# relay-set-d-latch.net
KiCad netlist of a schematic drawn in EAGLE
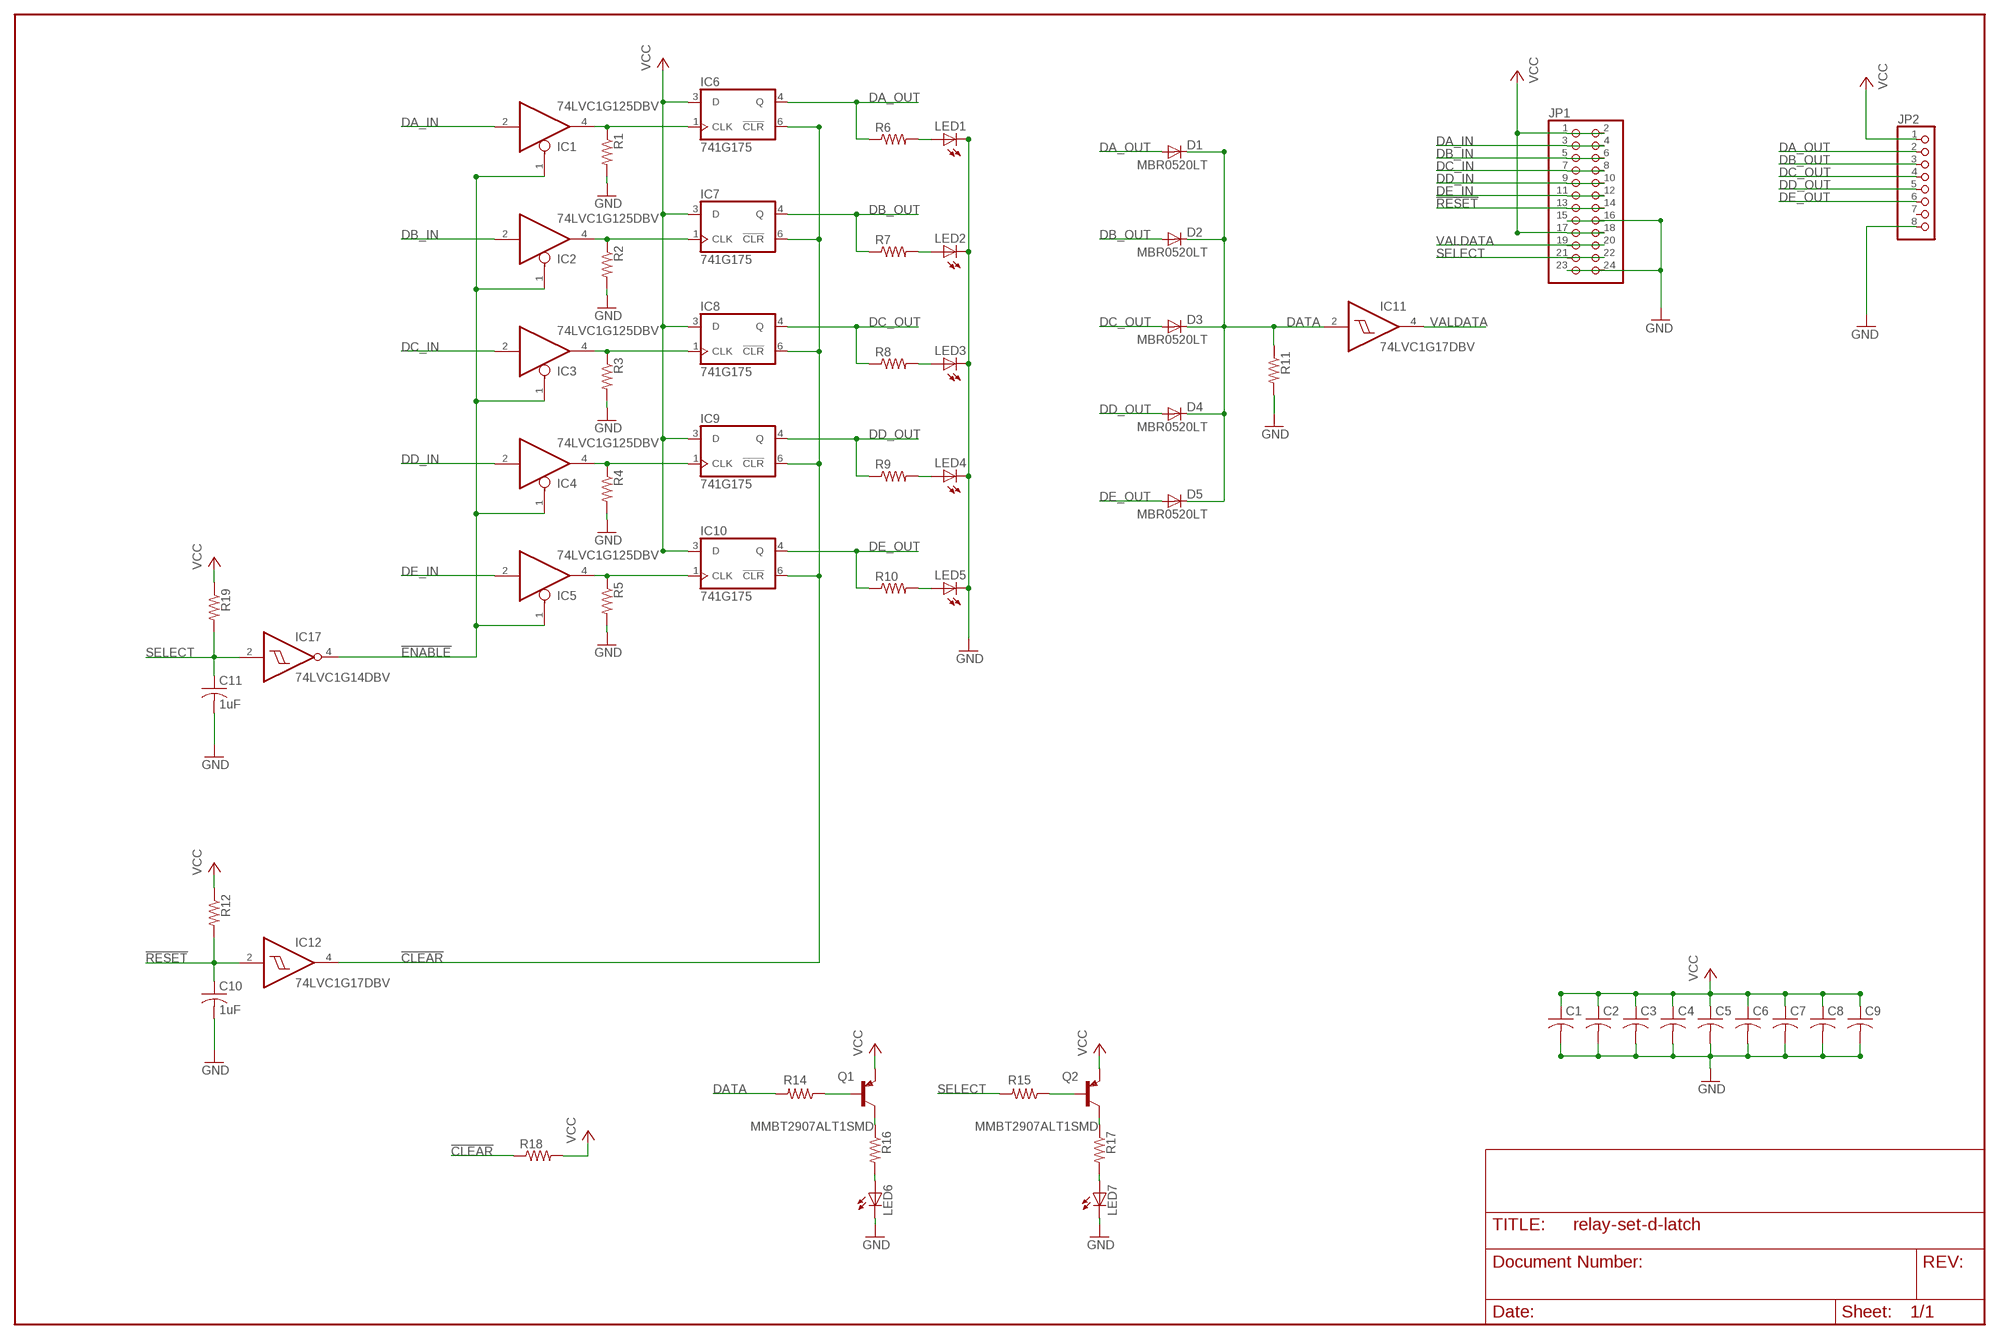
[diagram p0: schematic, sheet 1]

(export (version "E")
  (design (tool "Eeschema 10.0.6"))
  (components
    (comp (ref "C1")
      (value "C-USC0805")
      (footprint "eagle-import:C0805")
      (libsource (lib "eagle-import") (part "C-USC0805"))
    )
    (comp (ref "C2")
      (value "C-USC0805")
      (footprint "eagle-import:C0805")
      (libsource (lib "eagle-import") (part "C-USC0805"))
    )
    (comp (ref "C3")
      (value "C-USC0805")
      (footprint "eagle-import:C0805")
      (libsource (lib "eagle-import") (part "C-USC0805"))
    )
    (comp (ref "C4")
      (value "C-USC0805")
      (footprint "eagle-import:C0805")
      (libsource (lib "eagle-import") (part "C-USC0805"))
    )
    (comp (ref "C5")
      (value "C-USC0603K")
      (footprint "eagle-import:C0603K")
      (libsource (lib "eagle-import") (part "C-USC0603K"))
    )
    (comp (ref "C6")
      (value "C-USC0603K")
      (footprint "eagle-import:C0603K")
      (libsource (lib "eagle-import") (part "C-USC0603K"))
    )
    (comp (ref "C7")
      (value "C-USC0603K")
      (footprint "eagle-import:C0603K")
      (libsource (lib "eagle-import") (part "C-USC0603K"))
    )
    (comp (ref "C8")
      (value "C-USC0603K")
      (footprint "eagle-import:C0603K")
      (libsource (lib "eagle-import") (part "C-USC0603K"))
    )
    (comp (ref "C9")
      (value "C-USC0603K")
      (footprint "eagle-import:C0603K")
      (libsource (lib "eagle-import") (part "C-USC0603K"))
    )
    (comp (ref "C10")
      (value "1uF")
      (footprint "eagle-import:C0603K")
      (libsource (lib "eagle-import") (part "C-USC0603K"))
    )
    (comp (ref "C11")
      (value "1uF")
      (footprint "eagle-import:C0603K")
      (libsource (lib "eagle-import") (part "C-USC0603K"))
    )
    (comp (ref "D1")
      (value "MBR0520LT")
      (footprint "eagle-import:SOD123")
      (libsource (lib "eagle-import") (part "MBR0520LT"))
    )
    (comp (ref "D2")
      (value "MBR0520LT")
      (footprint "eagle-import:SOD123")
      (libsource (lib "eagle-import") (part "MBR0520LT"))
    )
    (comp (ref "D3")
      (value "MBR0520LT")
      (footprint "eagle-import:SOD123")
      (libsource (lib "eagle-import") (part "MBR0520LT"))
    )
    (comp (ref "D4")
      (value "MBR0520LT")
      (footprint "eagle-import:SOD123")
      (libsource (lib "eagle-import") (part "MBR0520LT"))
    )
    (comp (ref "D5")
      (value "MBR0520LT")
      (footprint "eagle-import:SOD123")
      (libsource (lib "eagle-import") (part "MBR0520LT"))
    )
    (comp (ref "IC1")
      (value "74LVC1G125DBV")
      (footprint "eagle-import:SOT23-5")
      (libsource (lib "eagle-import") (part "741G125DBVLVC"))
    )
    (comp (ref "IC2")
      (value "74LVC1G125DBV")
      (footprint "eagle-import:SOT23-5")
      (libsource (lib "eagle-import") (part "741G125DBVLVC"))
    )
    (comp (ref "IC3")
      (value "74LVC1G125DBV")
      (footprint "eagle-import:SOT23-5")
      (libsource (lib "eagle-import") (part "741G125DBVLVC"))
    )
    (comp (ref "IC4")
      (value "74LVC1G125DBV")
      (footprint "eagle-import:SOT23-5")
      (libsource (lib "eagle-import") (part "741G125DBVLVC"))
    )
    (comp (ref "IC5")
      (value "74LVC1G125DBV")
      (footprint "eagle-import:SOT23-5")
      (libsource (lib "eagle-import") (part "741G125DBVLVC"))
    )
    (comp (ref "IC6")
      (value "741G175")
      (footprint "eagle-import:DBV_R-PDSO-G6")
      (libsource (lib "eagle-import") (part "741G175"))
    )
    (comp (ref "IC7")
      (value "741G175")
      (footprint "eagle-import:DBV_R-PDSO-G6")
      (libsource (lib "eagle-import") (part "741G175"))
    )
    (comp (ref "IC8")
      (value "741G175")
      (footprint "eagle-import:DBV_R-PDSO-G6")
      (libsource (lib "eagle-import") (part "741G175"))
    )
    (comp (ref "IC9")
      (value "741G175")
      (footprint "eagle-import:DBV_R-PDSO-G6")
      (libsource (lib "eagle-import") (part "741G175"))
    )
    (comp (ref "IC10")
      (value "741G175")
      (footprint "eagle-import:DBV_R-PDSO-G6")
      (libsource (lib "eagle-import") (part "741G175"))
    )
    (comp (ref "IC11")
      (value "74LVC1G17DBV")
      (footprint "eagle-import:SOT23-5")
      (libsource (lib "eagle-import") (part "741G17DBVLVC"))
    )
    (comp (ref "IC12")
      (value "74LVC1G17DBV")
      (footprint "eagle-import:SOT23-5")
      (libsource (lib "eagle-import") (part "741G17DBVLVC"))
    )
    (comp (ref "IC17")
      (value "74LVC1G14DBV")
      (footprint "eagle-import:SOT23-5")
      (libsource (lib "eagle-import") (part "741G14DBVLVC"))
    )
    (comp (ref "JP1")
      (value "PINHD-2X12")
      (footprint "eagle-import:2X12")
      (libsource (lib "eagle-import") (part "PINHD-2X12"))
    )
    (comp (ref "JP2")
      (value "PINHD-1X8")
      (footprint "eagle-import:1X08")
      (libsource (lib "eagle-import") (part "PINHD-1X8"))
    )
    (comp (ref "LED1")
      (value "LEDCHIP-LED0805")
      (footprint "eagle-import:CHIP-LED0805")
      (libsource (lib "eagle-import") (part "LEDCHIP-LED0805"))
    )
    (comp (ref "LED2")
      (value "LEDCHIP-LED0805")
      (footprint "eagle-import:CHIP-LED0805")
      (libsource (lib "eagle-import") (part "LEDCHIP-LED0805"))
    )
    (comp (ref "LED3")
      (value "LEDCHIP-LED0805")
      (footprint "eagle-import:CHIP-LED0805")
      (libsource (lib "eagle-import") (part "LEDCHIP-LED0805"))
    )
    (comp (ref "LED4")
      (value "LEDCHIP-LED0805")
      (footprint "eagle-import:CHIP-LED0805")
      (libsource (lib "eagle-import") (part "LEDCHIP-LED0805"))
    )
    (comp (ref "LED5")
      (value "LEDCHIP-LED0805")
      (footprint "eagle-import:CHIP-LED0805")
      (libsource (lib "eagle-import") (part "LEDCHIP-LED0805"))
    )
    (comp (ref "LED6")
      (value "LEDCHIP-LED0805")
      (footprint "eagle-import:CHIP-LED0805")
      (libsource (lib "eagle-import") (part "LEDCHIP-LED0805"))
    )
    (comp (ref "LED7")
      (value "LEDCHIP-LED0805")
      (footprint "eagle-import:CHIP-LED0805")
      (libsource (lib "eagle-import") (part "LEDCHIP-LED0805"))
    )
    (comp (ref "Q1")
      (value "MMBT2907ALT1SMD")
      (footprint "eagle-import:SOT23-BEC")
      (libsource (lib "eagle-import") (part "MMBT2907SMDALT1"))
    )
    (comp (ref "Q2")
      (value "MMBT2907ALT1SMD")
      (footprint "eagle-import:SOT23-BEC")
      (libsource (lib "eagle-import") (part "MMBT2907SMDALT1"))
    )
    (comp (ref "R1")
      (value "R-US_R0805")
      (footprint "eagle-import:R0805")
      (libsource (lib "eagle-import") (part "R-US_R0805"))
    )
    (comp (ref "R2")
      (value "R-US_R0805")
      (footprint "eagle-import:R0805")
      (libsource (lib "eagle-import") (part "R-US_R0805"))
    )
    (comp (ref "R3")
      (value "R-US_R0805")
      (footprint "eagle-import:R0805")
      (libsource (lib "eagle-import") (part "R-US_R0805"))
    )
    (comp (ref "R4")
      (value "R-US_R0805")
      (footprint "eagle-import:R0805")
      (libsource (lib "eagle-import") (part "R-US_R0805"))
    )
    (comp (ref "R5")
      (value "R-US_R0805")
      (footprint "eagle-import:R0805")
      (libsource (lib "eagle-import") (part "R-US_R0805"))
    )
    (comp (ref "R6")
      (value "R-US_R0805")
      (footprint "eagle-import:R0805")
      (libsource (lib "eagle-import") (part "R-US_R0805"))
    )
    (comp (ref "R7")
      (value "R-US_R0805")
      (footprint "eagle-import:R0805")
      (libsource (lib "eagle-import") (part "R-US_R0805"))
    )
    (comp (ref "R8")
      (value "R-US_R0805")
      (footprint "eagle-import:R0805")
      (libsource (lib "eagle-import") (part "R-US_R0805"))
    )
    (comp (ref "R9")
      (value "R-US_R0805")
      (footprint "eagle-import:R0805")
      (libsource (lib "eagle-import") (part "R-US_R0805"))
    )
    (comp (ref "R10")
      (value "R-US_R0805")
      (footprint "eagle-import:R0805")
      (libsource (lib "eagle-import") (part "R-US_R0805"))
    )
    (comp (ref "R11")
      (value "R-US_R0805")
      (footprint "eagle-import:R0805")
      (libsource (lib "eagle-import") (part "R-US_R0805"))
    )
    (comp (ref "R12")
      (value "R-US_R0805")
      (footprint "eagle-import:R0805")
      (libsource (lib "eagle-import") (part "R-US_R0805"))
    )
    (comp (ref "R14")
      (value "R-US_R0805")
      (footprint "eagle-import:R0805")
      (libsource (lib "eagle-import") (part "R-US_R0805"))
    )
    (comp (ref "R15")
      (value "R-US_R0805")
      (footprint "eagle-import:R0805")
      (libsource (lib "eagle-import") (part "R-US_R0805"))
    )
    (comp (ref "R16")
      (value "R-US_R0805")
      (footprint "eagle-import:R0805")
      (libsource (lib "eagle-import") (part "R-US_R0805"))
    )
    (comp (ref "R17")
      (value "R-US_R0805")
      (footprint "eagle-import:R0805")
      (libsource (lib "eagle-import") (part "R-US_R0805"))
    )
    (comp (ref "R18")
      (value "R-US_R0805")
      (footprint "eagle-import:R0805")
      (libsource (lib "eagle-import") (part "R-US_R0805"))
    )
    (comp (ref "R19")
      (value "R-US_R0805")
      (footprint "eagle-import:R0805")
      (libsource (lib "eagle-import") (part "R-US_R0805"))
    )
  )
  (nets
    (net (code "1") (name "/DATA") (class "Default")
      (node (ref "D1") (pin "C") (pinfunction "C_C") (pintype "passive"))
      (node (ref "D2") (pin "C") (pinfunction "C_C") (pintype "passive"))
      (node (ref "D3") (pin "C") (pinfunction "C_C") (pintype "passive"))
      (node (ref "D4") (pin "C") (pinfunction "C_C") (pintype "passive"))
      (node (ref "D5") (pin "C") (pinfunction "C_C") (pintype "passive"))
      (node (ref "IC11") (pin "2") (pinfunction "I_2") (pintype "input"))
      (node (ref "R11") (pin "1") (pinfunction "1_1") (pintype "passive"))
      (node (ref "R14") (pin "2") (pinfunction "2_2") (pintype "passive"))
    )
    (net (code "2") (name "/DA_IN") (class "Default")
      (node (ref "IC1") (pin "2") (pinfunction "I_2") (pintype "input"))
      (node (ref "JP1") (pin "3") (pinfunction "3_3") (pintype "passive"))
      (node (ref "JP1") (pin "4") (pinfunction "4_4") (pintype "passive"))
    )
    (net (code "3") (name "/DA_OUT") (class "Default")
      (node (ref "D1") (pin "A") (pinfunction "A_A") (pintype "passive"))
      (node (ref "IC6") (pin "4") (pinfunction "Q_4") (pintype "output"))
      (node (ref "JP2") (pin "2") (pinfunction "2_2") (pintype "passive"))
      (node (ref "R6") (pin "1") (pinfunction "1_1") (pintype "passive"))
    )
    (net (code "4") (name "/DB_IN") (class "Default")
      (node (ref "IC2") (pin "2") (pinfunction "I_2") (pintype "input"))
      (node (ref "JP1") (pin "5") (pinfunction "5_5") (pintype "passive"))
      (node (ref "JP1") (pin "6") (pinfunction "6_6") (pintype "passive"))
    )
    (net (code "5") (name "/DB_OUT") (class "Default")
      (node (ref "D2") (pin "A") (pinfunction "A_A") (pintype "passive"))
      (node (ref "IC7") (pin "4") (pinfunction "Q_4") (pintype "output"))
      (node (ref "JP2") (pin "3") (pinfunction "3_3") (pintype "passive"))
      (node (ref "R7") (pin "1") (pinfunction "1_1") (pintype "passive"))
    )
    (net (code "6") (name "/DC_IN") (class "Default")
      (node (ref "IC3") (pin "2") (pinfunction "I_2") (pintype "input"))
      (node (ref "JP1") (pin "7") (pinfunction "7_7") (pintype "passive"))
      (node (ref "JP1") (pin "8") (pinfunction "8_8") (pintype "passive"))
    )
    (net (code "7") (name "/DC_OUT") (class "Default")
      (node (ref "D3") (pin "A") (pinfunction "A_A") (pintype "passive"))
      (node (ref "IC8") (pin "4") (pinfunction "Q_4") (pintype "output"))
      (node (ref "JP2") (pin "4") (pinfunction "4_4") (pintype "passive"))
      (node (ref "R8") (pin "1") (pinfunction "1_1") (pintype "passive"))
    )
    (net (code "8") (name "/DD_IN") (class "Default")
      (node (ref "IC4") (pin "2") (pinfunction "I_2") (pintype "input"))
      (node (ref "JP1") (pin "10") (pinfunction "10_10") (pintype "passive"))
      (node (ref "JP1") (pin "9") (pinfunction "9_9") (pintype "passive"))
    )
    (net (code "9") (name "/DD_OUT") (class "Default")
      (node (ref "D4") (pin "A") (pinfunction "A_A") (pintype "passive"))
      (node (ref "IC9") (pin "4") (pinfunction "Q_4") (pintype "output"))
      (node (ref "JP2") (pin "5") (pinfunction "5_5") (pintype "passive"))
      (node (ref "R9") (pin "1") (pinfunction "1_1") (pintype "passive"))
    )
    (net (code "10") (name "/DE_IN") (class "Default")
      (node (ref "IC5") (pin "2") (pinfunction "I_2") (pintype "input"))
      (node (ref "JP1") (pin "11") (pinfunction "11_11") (pintype "passive"))
      (node (ref "JP1") (pin "12") (pinfunction "12_12") (pintype "passive"))
    )
    (net (code "11") (name "/DE_OUT") (class "Default")
      (node (ref "D5") (pin "A") (pinfunction "A_A") (pintype "passive"))
      (node (ref "IC10") (pin "4") (pinfunction "Q_4") (pintype "output"))
      (node (ref "JP2") (pin "6") (pinfunction "6_6") (pintype "passive"))
      (node (ref "R10") (pin "1") (pinfunction "1_1") (pintype "passive"))
    )
    (net (code "12") (name "/SELECT") (class "Default")
      (node (ref "C11") (pin "1") (pinfunction "1_1") (pintype "passive"))
      (node (ref "IC17") (pin "2") (pinfunction "I_2") (pintype "input"))
      (node (ref "JP1") (pin "21") (pinfunction "21_21") (pintype "passive"))
      (node (ref "JP1") (pin "22") (pinfunction "22_22") (pintype "passive"))
      (node (ref "R15") (pin "2") (pinfunction "2_2") (pintype "passive"))
      (node (ref "R19") (pin "2") (pinfunction "2_2") (pintype "passive"))
    )
    (net (code "13") (name "/VALDATA") (class "Default")
      (node (ref "IC11") (pin "4") (pinfunction "O_4") (pintype "output"))
      (node (ref "JP1") (pin "19") (pinfunction "19_19") (pintype "passive"))
      (node (ref "JP1") (pin "20") (pinfunction "20_20") (pintype "passive"))
    )
    (net (code "14") (name "/~{CLEAR}") (class "Default")
      (node (ref "IC10") (pin "6") (pinfunction "~{CLR}_6") (pintype "output"))
      (node (ref "IC12") (pin "4") (pinfunction "O_4") (pintype "output"))
      (node (ref "IC6") (pin "6") (pinfunction "~{CLR}_6") (pintype "output"))
      (node (ref "IC7") (pin "6") (pinfunction "~{CLR}_6") (pintype "output"))
      (node (ref "IC8") (pin "6") (pinfunction "~{CLR}_6") (pintype "output"))
      (node (ref "IC9") (pin "6") (pinfunction "~{CLR}_6") (pintype "output"))
      (node (ref "R18") (pin "1") (pinfunction "1_1") (pintype "passive"))
    )
    (net (code "15") (name "/~{ENABLE}") (class "Default")
      (node (ref "IC1") (pin "1") (pinfunction "OE_1") (pintype "input"))
      (node (ref "IC17") (pin "4") (pinfunction "O_4") (pintype "output"))
      (node (ref "IC2") (pin "1") (pinfunction "OE_1") (pintype "input"))
      (node (ref "IC3") (pin "1") (pinfunction "OE_1") (pintype "input"))
      (node (ref "IC4") (pin "1") (pinfunction "OE_1") (pintype "input"))
      (node (ref "IC5") (pin "1") (pinfunction "OE_1") (pintype "input"))
    )
    (net (code "16") (name "/~{RESET}") (class "Default")
      (node (ref "C10") (pin "1") (pinfunction "1_1") (pintype "passive"))
      (node (ref "IC12") (pin "2") (pinfunction "I_2") (pintype "input"))
      (node (ref "JP1") (pin "13") (pinfunction "13_13") (pintype "passive"))
      (node (ref "JP1") (pin "14") (pinfunction "14_14") (pintype "passive"))
      (node (ref "R12") (pin "2") (pinfunction "2_2") (pintype "passive"))
    )
    (net (code "17") (name "GND") (class "Default")
      (node (ref "C1") (pin "2") (pinfunction "2_2") (pintype "passive"))
      (node (ref "C10") (pin "2") (pinfunction "2_2") (pintype "passive"))
      (node (ref "C11") (pin "2") (pinfunction "2_2") (pintype "passive"))
      (node (ref "C2") (pin "2") (pinfunction "2_2") (pintype "passive"))
      (node (ref "C3") (pin "2") (pinfunction "2_2") (pintype "passive"))
      (node (ref "C4") (pin "2") (pinfunction "2_2") (pintype "passive"))
      (node (ref "C5") (pin "2") (pinfunction "2_2") (pintype "passive"))
      (node (ref "C6") (pin "2") (pinfunction "2_2") (pintype "passive"))
      (node (ref "C7") (pin "2") (pinfunction "2_2") (pintype "passive"))
      (node (ref "C8") (pin "2") (pinfunction "2_2") (pintype "passive"))
      (node (ref "C9") (pin "2") (pinfunction "2_2") (pintype "passive"))
      (node (ref "JP1") (pin "15") (pinfunction "15_15") (pintype "passive"))
      (node (ref "JP1") (pin "16") (pinfunction "16_16") (pintype "passive"))
      (node (ref "JP1") (pin "23") (pinfunction "23_23") (pintype "passive"))
      (node (ref "JP1") (pin "24") (pinfunction "24_24") (pintype "passive"))
      (node (ref "JP2") (pin "8") (pinfunction "8_8") (pintype "passive"))
      (node (ref "LED1") (pin "C") (pinfunction "C_C") (pintype "passive"))
      (node (ref "LED2") (pin "C") (pinfunction "C_C") (pintype "passive"))
      (node (ref "LED3") (pin "C") (pinfunction "C_C") (pintype "passive"))
      (node (ref "LED4") (pin "C") (pinfunction "C_C") (pintype "passive"))
      (node (ref "LED5") (pin "C") (pinfunction "C_C") (pintype "passive"))
      (node (ref "LED6") (pin "C") (pinfunction "C_C") (pintype "passive"))
      (node (ref "LED7") (pin "C") (pinfunction "C_C") (pintype "passive"))
      (node (ref "R1") (pin "2") (pinfunction "2_2") (pintype "passive"))
      (node (ref "R11") (pin "2") (pinfunction "2_2") (pintype "passive"))
      (node (ref "R2") (pin "2") (pinfunction "2_2") (pintype "passive"))
      (node (ref "R3") (pin "2") (pinfunction "2_2") (pintype "passive"))
      (node (ref "R4") (pin "2") (pinfunction "2_2") (pintype "passive"))
      (node (ref "R5") (pin "2") (pinfunction "2_2") (pintype "passive"))
    )
    (net (code "18") (name "Net-(IC1A-O)") (class "Default")
      (node (ref "IC1") (pin "4") (pinfunction "O_4") (pintype "tri_state"))
      (node (ref "IC6") (pin "1") (pinfunction "CLK_1") (pintype "input"))
      (node (ref "R1") (pin "1") (pinfunction "1_1") (pintype "passive"))
    )
    (net (code "19") (name "Net-(IC2A-O)") (class "Default")
      (node (ref "IC2") (pin "4") (pinfunction "O_4") (pintype "tri_state"))
      (node (ref "IC7") (pin "1") (pinfunction "CLK_1") (pintype "input"))
      (node (ref "R2") (pin "1") (pinfunction "1_1") (pintype "passive"))
    )
    (net (code "20") (name "Net-(IC3A-O)") (class "Default")
      (node (ref "IC3") (pin "4") (pinfunction "O_4") (pintype "tri_state"))
      (node (ref "IC8") (pin "1") (pinfunction "CLK_1") (pintype "input"))
      (node (ref "R3") (pin "1") (pinfunction "1_1") (pintype "passive"))
    )
    (net (code "21") (name "Net-(IC4A-O)") (class "Default")
      (node (ref "IC4") (pin "4") (pinfunction "O_4") (pintype "tri_state"))
      (node (ref "IC9") (pin "1") (pinfunction "CLK_1") (pintype "input"))
      (node (ref "R4") (pin "1") (pinfunction "1_1") (pintype "passive"))
    )
    (net (code "22") (name "Net-(IC10A-CLK)") (class "Default")
      (node (ref "IC10") (pin "1") (pinfunction "CLK_1") (pintype "input"))
      (node (ref "IC5") (pin "4") (pinfunction "O_4") (pintype "tri_state"))
      (node (ref "R5") (pin "1") (pinfunction "1_1") (pintype "passive"))
    )
    (net (code "23") (name "Net-(LED1-PadA)") (class "Default")
      (node (ref "LED1") (pin "A") (pinfunction "A_A") (pintype "passive"))
      (node (ref "R6") (pin "2") (pinfunction "2_2") (pintype "passive"))
    )
    (net (code "24") (name "Net-(LED2-PadA)") (class "Default")
      (node (ref "LED2") (pin "A") (pinfunction "A_A") (pintype "passive"))
      (node (ref "R7") (pin "2") (pinfunction "2_2") (pintype "passive"))
    )
    (net (code "25") (name "Net-(LED3-PadA)") (class "Default")
      (node (ref "LED3") (pin "A") (pinfunction "A_A") (pintype "passive"))
      (node (ref "R8") (pin "2") (pinfunction "2_2") (pintype "passive"))
    )
    (net (code "26") (name "Net-(LED4-PadA)") (class "Default")
      (node (ref "LED4") (pin "A") (pinfunction "A_A") (pintype "passive"))
      (node (ref "R9") (pin "2") (pinfunction "2_2") (pintype "passive"))
    )
    (net (code "27") (name "Net-(LED5-PadA)") (class "Default")
      (node (ref "LED5") (pin "A") (pinfunction "A_A") (pintype "passive"))
      (node (ref "R10") (pin "2") (pinfunction "2_2") (pintype "passive"))
    )
    (net (code "28") (name "Net-(LED6-PadA)") (class "Default")
      (node (ref "LED6") (pin "A") (pinfunction "A_A") (pintype "passive"))
      (node (ref "R16") (pin "2") (pinfunction "2_2") (pintype "passive"))
    )
    (net (code "29") (name "Net-(LED7-PadA)") (class "Default")
      (node (ref "LED7") (pin "A") (pinfunction "A_A") (pintype "passive"))
      (node (ref "R17") (pin "2") (pinfunction "2_2") (pintype "passive"))
    )
    (net (code "30") (name "Net-(Q1-PadB)") (class "Default")
      (node (ref "Q1") (pin "B") (pinfunction "B_B") (pintype "passive"))
      (node (ref "R14") (pin "1") (pinfunction "1_1") (pintype "passive"))
    )
    (net (code "31") (name "Net-(Q1-PadC)") (class "Default")
      (node (ref "Q1") (pin "C") (pinfunction "C_C") (pintype "passive"))
      (node (ref "R16") (pin "1") (pinfunction "1_1") (pintype "passive"))
    )
    (net (code "32") (name "Net-(Q2-PadB)") (class "Default")
      (node (ref "Q2") (pin "B") (pinfunction "B_B") (pintype "passive"))
      (node (ref "R15") (pin "1") (pinfunction "1_1") (pintype "passive"))
    )
    (net (code "33") (name "Net-(Q2-PadC)") (class "Default")
      (node (ref "Q2") (pin "C") (pinfunction "C_C") (pintype "passive"))
      (node (ref "R17") (pin "1") (pinfunction "1_1") (pintype "passive"))
    )
    (net (code "34") (name "VCC") (class "Default")
      (node (ref "C1") (pin "1") (pinfunction "1_1") (pintype "passive"))
      (node (ref "C2") (pin "1") (pinfunction "1_1") (pintype "passive"))
      (node (ref "C3") (pin "1") (pinfunction "1_1") (pintype "passive"))
      (node (ref "C4") (pin "1") (pinfunction "1_1") (pintype "passive"))
      (node (ref "C5") (pin "1") (pinfunction "1_1") (pintype "passive"))
      (node (ref "C6") (pin "1") (pinfunction "1_1") (pintype "passive"))
      (node (ref "C7") (pin "1") (pinfunction "1_1") (pintype "passive"))
      (node (ref "C8") (pin "1") (pinfunction "1_1") (pintype "passive"))
      (node (ref "C9") (pin "1") (pinfunction "1_1") (pintype "passive"))
      (node (ref "IC10") (pin "3") (pinfunction "D_3") (pintype "input"))
      (node (ref "IC6") (pin "3") (pinfunction "D_3") (pintype "input"))
      (node (ref "IC7") (pin "3") (pinfunction "D_3") (pintype "input"))
      (node (ref "IC8") (pin "3") (pinfunction "D_3") (pintype "input"))
      (node (ref "IC9") (pin "3") (pinfunction "D_3") (pintype "input"))
      (node (ref "JP1") (pin "1") (pinfunction "1_1") (pintype "passive"))
      (node (ref "JP1") (pin "17") (pinfunction "17_17") (pintype "passive"))
      (node (ref "JP1") (pin "18") (pinfunction "18_18") (pintype "passive"))
      (node (ref "JP1") (pin "2") (pinfunction "2_2") (pintype "passive"))
      (node (ref "JP2") (pin "1") (pinfunction "1_1") (pintype "passive"))
      (node (ref "Q1") (pin "E") (pinfunction "E_E") (pintype "passive"))
      (node (ref "Q2") (pin "E") (pinfunction "E_E") (pintype "passive"))
      (node (ref "R12") (pin "1") (pinfunction "1_1") (pintype "passive"))
      (node (ref "R18") (pin "2") (pinfunction "2_2") (pintype "passive"))
      (node (ref "R19") (pin "1") (pinfunction "1_1") (pintype "passive"))
    )
    (net (code "35") (name "unconnected-(JP2-Pad7)") (class "Default")
      (node (ref "JP2") (pin "7") (pinfunction "7_7") (pintype "passive"))
    )
  )
)
